# Board_4_Buttons_WS-TASV-4-IP67.net
KiCad netlist of a schematic drawn in EAGLE
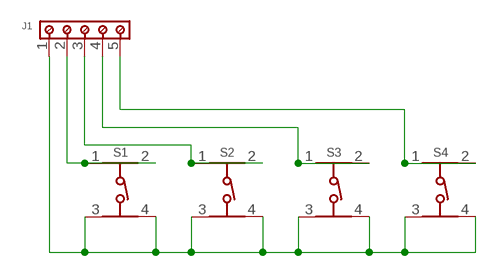
[diagram p0: schematic, sheet 1]

(export (version "E")
  (design (tool "Eeschema 10.0.6"))
  (components
    (comp (ref "J1")
      (value "691709710305")
      (footprint "eagle-import:691709710305")
      (libsource (lib "eagle-import") (part "691709710305"))
    )
    (comp (ref "S1")
      (value "430773034825")
      (footprint "eagle-import:430773034825")
      (libsource (lib "eagle-import") (part "430773034825"))
    )
    (comp (ref "S2")
      (value "430773034825")
      (footprint "eagle-import:430773034825")
      (libsource (lib "eagle-import") (part "430773034825"))
    )
    (comp (ref "S3")
      (value "430773034825")
      (footprint "eagle-import:430773034825")
      (libsource (lib "eagle-import") (part "430773034825"))
    )
    (comp (ref "S4")
      (value "430773034825")
      (footprint "eagle-import:430773034825")
      (libsource (lib "eagle-import") (part "430773034825"))
    )
  )
  (nets
    (net (code "1") (name "Net-(S1-2)") (class "Default")
      (node (ref "J1") (pin "1") (pinfunction "1_1") (pintype "passive"))
      (node (ref "S1") (pin "3") (pinfunction "2_3") (pintype "passive"))
      (node (ref "S1") (pin "4") (pinfunction "4_4") (pintype "passive"))
      (node (ref "S2") (pin "3") (pinfunction "2_3") (pintype "passive"))
      (node (ref "S2") (pin "4") (pinfunction "4_4") (pintype "passive"))
      (node (ref "S3") (pin "3") (pinfunction "2_3") (pintype "passive"))
      (node (ref "S3") (pin "4") (pinfunction "4_4") (pintype "passive"))
      (node (ref "S4") (pin "3") (pinfunction "2_3") (pintype "passive"))
      (node (ref "S4") (pin "4") (pinfunction "4_4") (pintype "passive"))
    )
    (net (code "2") (name "Net-(S1-3)") (class "Default")
      (node (ref "J1") (pin "2") (pinfunction "2_2") (pintype "passive"))
      (node (ref "S1") (pin "1") (pinfunction "1_1") (pintype "passive"))
      (node (ref "S1") (pin "2") (pinfunction "3_2") (pintype "passive"))
    )
    (net (code "3") (name "Net-(S2-3)") (class "Default")
      (node (ref "J1") (pin "3") (pinfunction "3_3") (pintype "passive"))
      (node (ref "S2") (pin "1") (pinfunction "1_1") (pintype "passive"))
      (node (ref "S2") (pin "2") (pinfunction "3_2") (pintype "passive"))
    )
    (net (code "4") (name "Net-(S3-3)") (class "Default")
      (node (ref "J1") (pin "4") (pinfunction "4_4") (pintype "passive"))
      (node (ref "S3") (pin "1") (pinfunction "1_1") (pintype "passive"))
      (node (ref "S3") (pin "2") (pinfunction "3_2") (pintype "passive"))
    )
    (net (code "5") (name "Net-(S4-3)") (class "Default")
      (node (ref "J1") (pin "5") (pinfunction "5_5") (pintype "passive"))
      (node (ref "S4") (pin "1") (pinfunction "1_1") (pintype "passive"))
      (node (ref "S4") (pin "2") (pinfunction "3_2") (pintype "passive"))
    )
  )
)
